# SCH_CarAccessoryKitV1_0.net
KiCad netlist of a schematic drawn in EasyEDA
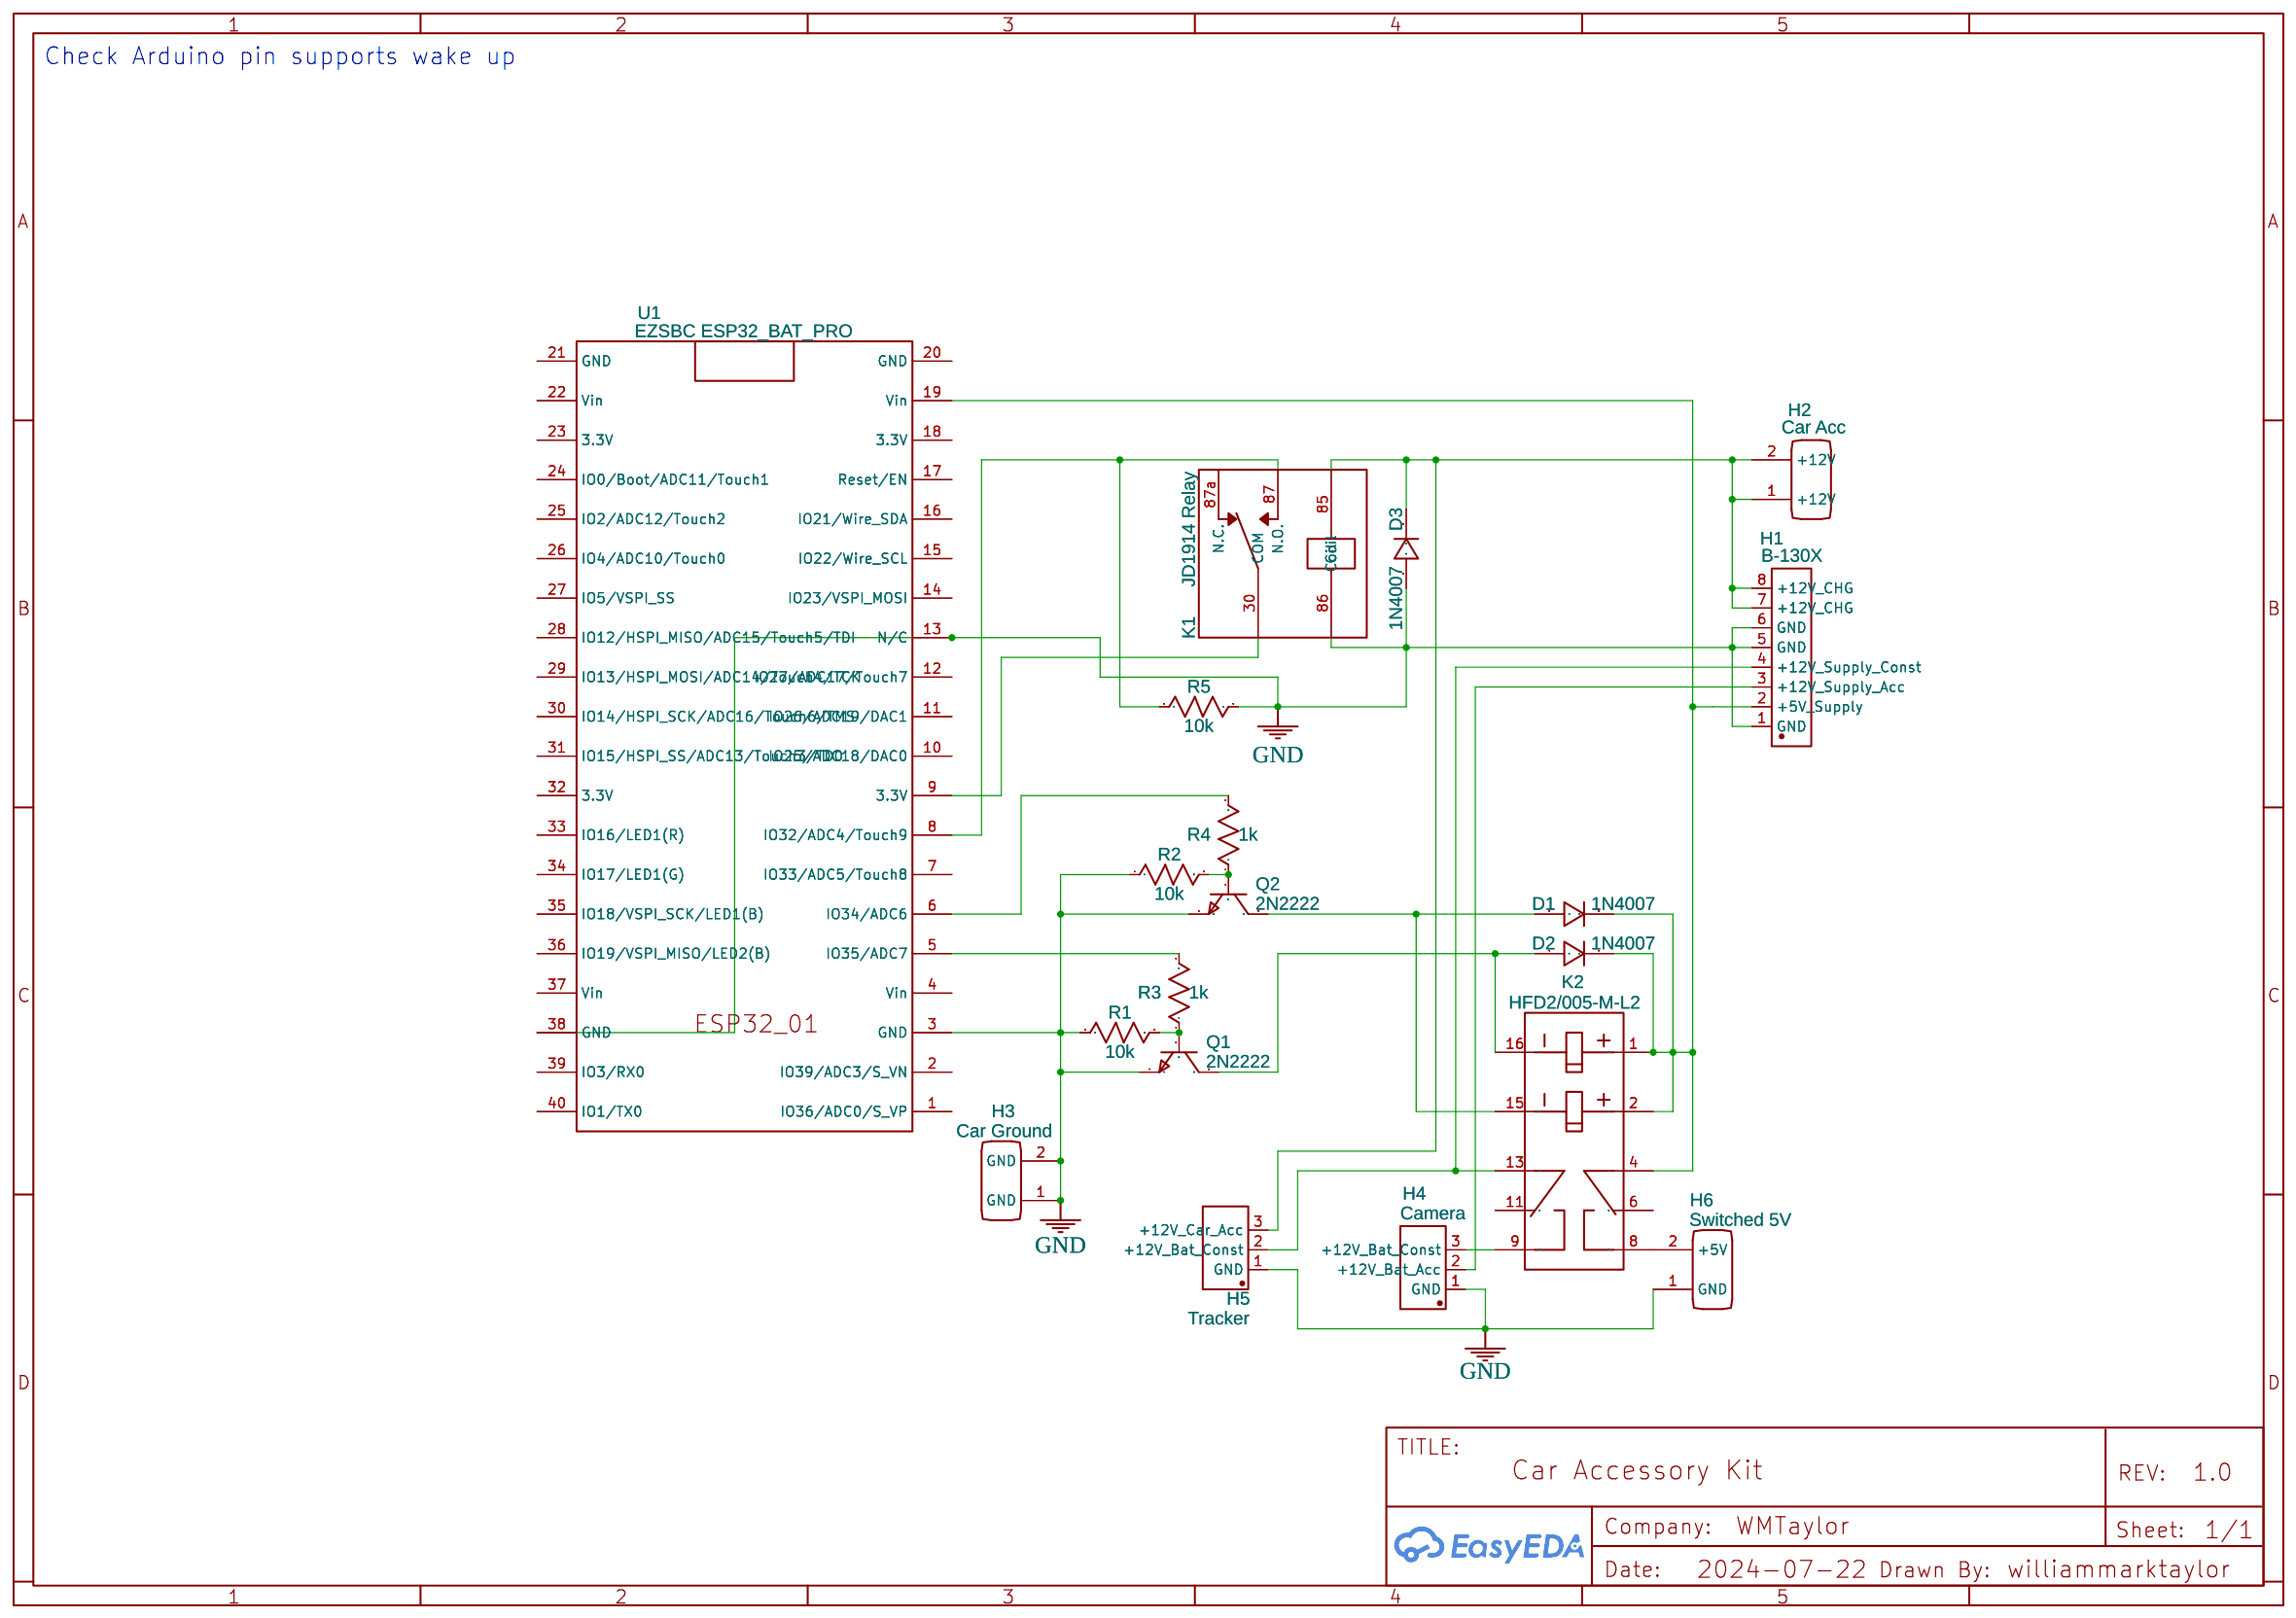
[diagram p0: schematic sheet]

(export (version "E")
  (design (tool "Eeschema 10.0.6"))
  (components
    (comp (ref "D1")
      (value "1N4007")
      (fields (field (name "Manufacturer") "SEMTECH"))
      (libsource (lib "") (part "1N4007"))
    )
    (comp (ref "D2")
      (value "1N4007")
      (fields (field (name "Manufacturer") "SEMTECH"))
      (libsource (lib "") (part "1N4007"))
    )
    (comp (ref "D3")
      (value "1N4007")
      (fields (field (name "Manufacturer") "SEMTECH"))
      (libsource (lib "") (part "1N4007_1"))
    )
    (comp (ref "H1")
      (value "B-130X")
      (fields (field (name "Manufacturer Part") "CH3.96-8A") (field (name "Manufacturer") "BOOMELE"))
      (libsource (lib "") (part "CH3.96-8A"))
    )
    (comp (ref "H2") (value "Car Acc") (libsource (lib "") (part "JST_VH-2P-3.96_1")))
    (comp (ref "H3") (value "Car Ground") (libsource (lib "") (part "JST_VH-2P-3.96_2")))
    (comp (ref "H4")
      (value "Camera")
      (fields (field (name "Manufacturer Part") "VH-3A") (field (name "Manufacturer") "BOOMELE(博穆精密)"))
      (libsource (lib "") (part "VH3.96-3A"))
    )
    (comp (ref "H5")
      (value "Tracker")
      (fields (field (name "Manufacturer Part") "VH-3A") (field (name "Manufacturer") "BOOMELE(博穆精密)"))
      (libsource (lib "") (part "VH3.96-3A_1"))
    )
    (comp (ref "H6") (value "Switched 5V") (libsource (lib "") (part "JST_VH-2P-3.96")))
    (comp (ref "K1")
      (value "JD1914 Relay")
      (fields (field (name "Manufacturer Part") "JD1914") (field (name "Manufacturer") "BenFeng"))
      (libsource (lib "") (part "RELAY JD1914 12V 80A"))
    )
    (comp (ref "K2")
      (value "HFD2/005-M-L2")
      (fields (field (name "Manufacturer") "HF(宏发)"))
      (libsource (lib "") (part "HFD2/005-M-L2"))
    )
    (comp (ref "Q1") (value "2N2222") (libsource (lib "") (part "2N2222")))
    (comp (ref "Q2") (value "2N2222") (libsource (lib "") (part "2N2222")))
    (comp (ref "R1") (value "10k") (libsource (lib "") (part "R_AXIAL-0.3_US")))
    (comp (ref "R2") (value "10k") (libsource (lib "") (part "R_AXIAL-0.3_US")))
    (comp (ref "R3") (value "1k") (libsource (lib "") (part "R_AXIAL-0.3_US_1")))
    (comp (ref "R4") (value "1k") (libsource (lib "") (part "R_AXIAL-0.3_US_1")))
    (comp (ref "R5") (value "10k") (libsource (lib "") (part "R_AXIAL-0.3_US")))
    (comp (ref "U1")
      (value "EZSBC ESP32_BAT_PRO")
      (fields (field (name "Manufacturer Part") "ESP32_01") (field (name "Manufacturer") "EZSBC"))
      (libsource (lib "") (part "EZSBC ESP32_01"))
    )
  )
  (nets
    (net (code "1") (name "GND") (class "Default")
      (node (ref "D3") (pin "2") (pinfunction "2_2") (pintype "unspecified"))
      (node (ref "H1") (pin "1") (pinfunction "GND_1") (pintype "unspecified"))
      (node (ref "H1") (pin "5") (pinfunction "GND_5") (pintype "unspecified"))
      (node (ref "H1") (pin "6") (pinfunction "GND_6") (pintype "unspecified"))
      (node (ref "H3") (pin "1") (pinfunction "GND_1") (pintype "unspecified"))
      (node (ref "H3") (pin "2") (pinfunction "GND_2") (pintype "unspecified"))
      (node (ref "H4") (pin "1") (pinfunction "GND_1") (pintype "unspecified"))
      (node (ref "H5") (pin "1") (pinfunction "GND_1") (pintype "unspecified"))
      (node (ref "H6") (pin "1") (pinfunction "GND_1") (pintype "unspecified"))
      (node (ref "K1") (pin "86") (pinfunction "Coil_86") (pintype "unspecified"))
      (node (ref "Q1") (pin "1") (pinfunction "E_1") (pintype "unspecified"))
      (node (ref "Q2") (pin "1") (pinfunction "E_1") (pintype "unspecified"))
      (node (ref "R1") (pin "1") (pinfunction "1_1") (pintype "unspecified"))
      (node (ref "R2") (pin "1") (pinfunction "1_1") (pintype "unspecified"))
      (node (ref "R5") (pin "2") (pinfunction "2_2") (pintype "unspecified"))
      (node (ref "U1") (pin "13") (pinfunction "N/C_13") (pintype "unspecified"))
      (node (ref "U1") (pin "3") (pinfunction "GND_3") (pintype "unspecified"))
      (node (ref "U1") (pin "38") (pinfunction "GND_38") (pintype "unspecified"))
    )
    (net (code "2") (name "Net-(H1-+5V_Supply)") (class "Default")
      (node (ref "D1") (pin "1") (pinfunction "1_1") (pintype "unspecified"))
      (node (ref "D2") (pin "1") (pinfunction "1_1") (pintype "unspecified"))
      (node (ref "H1") (pin "2") (pinfunction "+5V_Supply_2") (pintype "unspecified"))
      (node (ref "K2") (pin "1") (pinfunction "1_1") (pintype "unspecified"))
      (node (ref "K2") (pin "2") (pinfunction "2_2") (pintype "unspecified"))
      (node (ref "K2") (pin "4") (pinfunction "4_4") (pintype "unspecified"))
      (node (ref "U1") (pin "19") (pinfunction "Vin_19") (pintype "unspecified"))
    )
    (net (code "3") (name "Net-(H1-+12V_Supply_Acc)") (class "Default")
      (node (ref "H1") (pin "3") (pinfunction "+12V_Supply_Acc_3") (pintype "unspecified"))
      (node (ref "H4") (pin "2") (pinfunction "+12V_Bat_Acc_2") (pintype "unspecified"))
    )
    (net (code "4") (name "Net-(H1-+12V_Supply_Const)") (class "Default")
      (node (ref "H1") (pin "4") (pinfunction "+12V_Supply_Const_4") (pintype "unspecified"))
      (node (ref "H5") (pin "2") (pinfunction "+12V_Bat_Const_2") (pintype "unspecified"))
      (node (ref "K2") (pin "13") (pinfunction "13_13") (pintype "unspecified"))
    )
    (net (code "5") (name "Net-(H4-+12V_Bat_Const)") (class "Default")
      (node (ref "H4") (pin "3") (pinfunction "+12V_Bat_Const_3") (pintype "unspecified"))
      (node (ref "K2") (pin "9") (pinfunction "9_9") (pintype "unspecified"))
    )
    (net (code "6") (name "Net-(H5-+12V_Car_Acc)") (class "Default")
      (node (ref "D3") (pin "1") (pinfunction "1_1") (pintype "unspecified"))
      (node (ref "H1") (pin "7") (pinfunction "+12V_CHG_7") (pintype "unspecified"))
      (node (ref "H1") (pin "8") (pinfunction "+12V_CHG_8") (pintype "unspecified"))
      (node (ref "H2") (pin "1") (pinfunction "+12V_1") (pintype "unspecified"))
      (node (ref "H2") (pin "2") (pinfunction "+12V_2") (pintype "unspecified"))
      (node (ref "H5") (pin "3") (pinfunction "+12V_Car_Acc_3") (pintype "unspecified"))
      (node (ref "K1") (pin "85") (pinfunction "Coil_85") (pintype "unspecified"))
    )
    (net (code "7") (name "Net-(H6-+5V)") (class "Default")
      (node (ref "H6") (pin "2") (pinfunction "+5V_2") (pintype "unspecified"))
      (node (ref "K2") (pin "8") (pinfunction "8_8") (pintype "unspecified"))
    )
    (net (code "8") (name "Net-(K1-COM)") (class "Default")
      (node (ref "K1") (pin "30") (pinfunction "COM_30") (pintype "unspecified"))
      (node (ref "U1") (pin "9") (pinfunction "3.3V_9") (pintype "unspecified"))
    )
    (net (code "9") (name "Net-(K1-N.O.)") (class "Default")
      (node (ref "K1") (pin "87") (pinfunction "N.O._87") (pintype "unspecified"))
      (node (ref "R5") (pin "1") (pinfunction "1_1") (pintype "unspecified"))
      (node (ref "U1") (pin "8") (pinfunction "IO32/ADC4/Touch9_8") (pintype "unspecified"))
    )
    (net (code "10") (name "Net-(Q1-B)") (class "Default")
      (node (ref "Q1") (pin "2") (pinfunction "B_2") (pintype "unspecified"))
      (node (ref "R1") (pin "2") (pinfunction "2_2") (pintype "unspecified"))
      (node (ref "R3") (pin "1") (pinfunction "1_1") (pintype "unspecified"))
    )
    (net (code "11") (name "Net-(Q1-C)") (class "Default")
      (node (ref "D2") (pin "2") (pinfunction "2_2") (pintype "unspecified"))
      (node (ref "K2") (pin "16") (pinfunction "16_16") (pintype "unspecified"))
      (node (ref "Q1") (pin "3") (pinfunction "C_3") (pintype "unspecified"))
    )
    (net (code "12") (name "Net-(Q2-B)") (class "Default")
      (node (ref "Q2") (pin "2") (pinfunction "B_2") (pintype "unspecified"))
      (node (ref "R2") (pin "2") (pinfunction "2_2") (pintype "unspecified"))
      (node (ref "R4") (pin "1") (pinfunction "1_1") (pintype "unspecified"))
    )
    (net (code "13") (name "Net-(Q2-C)") (class "Default")
      (node (ref "D1") (pin "2") (pinfunction "2_2") (pintype "unspecified"))
      (node (ref "K2") (pin "15") (pinfunction "15_15") (pintype "unspecified"))
      (node (ref "Q2") (pin "3") (pinfunction "C_3") (pintype "unspecified"))
    )
    (net (code "14") (name "Net-(U1-IO34{slash}ADC6)") (class "Default")
      (node (ref "R4") (pin "2") (pinfunction "2_2") (pintype "unspecified"))
      (node (ref "U1") (pin "6") (pinfunction "IO34/ADC6_6") (pintype "unspecified"))
    )
    (net (code "15") (name "Net-(U1-IO35{slash}ADC7)") (class "Default")
      (node (ref "R3") (pin "2") (pinfunction "2_2") (pintype "unspecified"))
      (node (ref "U1") (pin "5") (pinfunction "IO35/ADC7_5") (pintype "unspecified"))
    )
    (net (code "16") (name "unconnected-(K1-N.C.-Pad87a)") (class "Default")
      (node (ref "K1") (pin "87a") (pinfunction "N.C._87a") (pintype "unspecified"))
    )
    (net (code "17") (name "unconnected-(K2-Pad6)") (class "Default")
      (node (ref "K2") (pin "6") (pinfunction "6_6") (pintype "unspecified"))
    )
    (net (code "18") (name "unconnected-(K2-Pad11)") (class "Default")
      (node (ref "K2") (pin "11") (pinfunction "11_11") (pintype "unspecified"))
    )
    (net (code "19") (name "unconnected-(U1-3.3V-Pad18)") (class "Default")
      (node (ref "U1") (pin "18") (pinfunction "3.3V_18") (pintype "unspecified"))
    )
    (net (code "20") (name "unconnected-(U1-3.3V-Pad23)") (class "Default")
      (node (ref "U1") (pin "23") (pinfunction "3.3V_23") (pintype "unspecified"))
    )
    (net (code "21") (name "unconnected-(U1-3.3V-Pad32)") (class "Default")
      (node (ref "U1") (pin "32") (pinfunction "3.3V_32") (pintype "unspecified"))
    )
    (net (code "22") (name "unconnected-(U1-GND-Pad20)") (class "Default")
      (node (ref "U1") (pin "20") (pinfunction "GND_20") (pintype "unspecified"))
    )
    (net (code "23") (name "unconnected-(U1-GND-Pad21)") (class "Default")
      (node (ref "U1") (pin "21") (pinfunction "GND_21") (pintype "unspecified"))
    )
    (net (code "24") (name "unconnected-(U1-IO0{slash}Boot{slash}ADC11{slash}Touch1-Pad24)") (class "Default")
      (node (ref "U1") (pin "24") (pinfunction "IO0/Boot/ADC11/Touch1_24") (pintype "unspecified"))
    )
    (net (code "25") (name "unconnected-(U1-IO1{slash}TX0-Pad40)") (class "Default")
      (node (ref "U1") (pin "40") (pinfunction "IO1/TX0_40") (pintype "unspecified"))
    )
    (net (code "26") (name "unconnected-(U1-IO2{slash}ADC12{slash}Touch2-Pad25)") (class "Default")
      (node (ref "U1") (pin "25") (pinfunction "IO2/ADC12/Touch2_25") (pintype "unspecified"))
    )
    (net (code "27") (name "unconnected-(U1-IO3{slash}RX0-Pad39)") (class "Default")
      (node (ref "U1") (pin "39") (pinfunction "IO3/RX0_39") (pintype "unspecified"))
    )
    (net (code "28") (name "unconnected-(U1-IO4{slash}ADC10{slash}Touch0-Pad26)") (class "Default")
      (node (ref "U1") (pin "26") (pinfunction "IO4/ADC10/Touch0_26") (pintype "unspecified"))
    )
    (net (code "29") (name "unconnected-(U1-IO5{slash}VSPI_SS-Pad27)") (class "Default")
      (node (ref "U1") (pin "27") (pinfunction "IO5/VSPI_SS_27") (pintype "unspecified"))
    )
    (net (code "30") (name "unconnected-(U1-IO12{slash}HSPI_MISO{slash}ADC15{slash}Touch5{slash}TDI-Pad28)") (class "Default")
      (node (ref "U1") (pin "28") (pinfunction "IO12/HSPI_MISO/ADC15/Touch5/TDI_28") (pintype "unspecified"))
    )
    (net (code "31") (name "unconnected-(U1-IO13{slash}HSPI_MOSI{slash}ADC14{slash}Touch4{slash}TCK-Pad29)") (class "Default")
      (node (ref "U1") (pin "29") (pinfunction "IO13/HSPI_MOSI/ADC14/Touch4/TCK_29") (pintype "unspecified"))
    )
    (net (code "32") (name "unconnected-(U1-IO14{slash}HSPI_SCK{slash}ADC16{slash}Touch6{slash}TMS-Pad30)") (class "Default")
      (node (ref "U1") (pin "30") (pinfunction "IO14/HSPI_SCK/ADC16/Touch6/TMS_30") (pintype "unspecified"))
    )
    (net (code "33") (name "unconnected-(U1-IO15{slash}HSPI_SS{slash}ADC13{slash}Touch3{slash}TD0-Pad31)") (class "Default")
      (node (ref "U1") (pin "31") (pinfunction "IO15/HSPI_SS/ADC13/Touch3/TD0_31") (pintype "unspecified"))
    )
    (net (code "34") (name "unconnected-(U1-IO16{slash}LED1(R)-Pad33)") (class "Default")
      (node (ref "U1") (pin "33") (pinfunction "IO16/LED1(R)_33") (pintype "unspecified"))
    )
    (net (code "35") (name "unconnected-(U1-IO17{slash}LED1(G)-Pad34)") (class "Default")
      (node (ref "U1") (pin "34") (pinfunction "IO17/LED1(G)_34") (pintype "unspecified"))
    )
    (net (code "36") (name "unconnected-(U1-IO18{slash}VSPI_SCK{slash}LED1(B)-Pad35)") (class "Default")
      (node (ref "U1") (pin "35") (pinfunction "IO18/VSPI_SCK/LED1(B)_35") (pintype "unspecified"))
    )
    (net (code "37") (name "unconnected-(U1-IO19{slash}VSPI_MISO{slash}LED2(B)-Pad36)") (class "Default")
      (node (ref "U1") (pin "36") (pinfunction "IO19/VSPI_MISO/LED2(B)_36") (pintype "unspecified"))
    )
    (net (code "38") (name "unconnected-(U1-IO21{slash}Wire_SDA-Pad16)") (class "Default")
      (node (ref "U1") (pin "16") (pinfunction "IO21/Wire_SDA_16") (pintype "unspecified"))
    )
    (net (code "39") (name "unconnected-(U1-IO22{slash}Wire_SCL-Pad15)") (class "Default")
      (node (ref "U1") (pin "15") (pinfunction "IO22/Wire_SCL_15") (pintype "unspecified"))
    )
    (net (code "40") (name "unconnected-(U1-IO23{slash}VSPI_MOSI-Pad14)") (class "Default")
      (node (ref "U1") (pin "14") (pinfunction "IO23/VSPI_MOSI_14") (pintype "unspecified"))
    )
    (net (code "41") (name "unconnected-(U1-IO25{slash}ADC18{slash}DAC0-Pad10)") (class "Default")
      (node (ref "U1") (pin "10") (pinfunction "IO25/ADC18/DAC0_10") (pintype "unspecified"))
    )
    (net (code "42") (name "unconnected-(U1-IO26{slash}ADC19{slash}DAC1-Pad11)") (class "Default")
      (node (ref "U1") (pin "11") (pinfunction "IO26/ADC19/DAC1_11") (pintype "unspecified"))
    )
    (net (code "43") (name "unconnected-(U1-IO27{slash}ADC17{slash}Touch7-Pad12)") (class "Default")
      (node (ref "U1") (pin "12") (pinfunction "IO27/ADC17/Touch7_12") (pintype "unspecified"))
    )
    (net (code "44") (name "unconnected-(U1-IO33{slash}ADC5{slash}Touch8-Pad7)") (class "Default")
      (node (ref "U1") (pin "7") (pinfunction "IO33/ADC5/Touch8_7") (pintype "unspecified"))
    )
    (net (code "45") (name "unconnected-(U1-IO36{slash}ADC0{slash}S_VP-Pad1)") (class "Default")
      (node (ref "U1") (pin "1") (pinfunction "IO36/ADC0/S_VP_1") (pintype "unspecified"))
    )
    (net (code "46") (name "unconnected-(U1-IO39{slash}ADC3{slash}S_VN-Pad2)") (class "Default")
      (node (ref "U1") (pin "2") (pinfunction "IO39/ADC3/S_VN_2") (pintype "unspecified"))
    )
    (net (code "47") (name "unconnected-(U1-Reset{slash}EN-Pad17)") (class "Default")
      (node (ref "U1") (pin "17") (pinfunction "Reset/EN_17") (pintype "unspecified"))
    )
    (net (code "48") (name "unconnected-(U1-Vin-Pad4)") (class "Default")
      (node (ref "U1") (pin "4") (pinfunction "Vin_4") (pintype "unspecified"))
    )
    (net (code "49") (name "unconnected-(U1-Vin-Pad22)") (class "Default")
      (node (ref "U1") (pin "22") (pinfunction "Vin_22") (pintype "unspecified"))
    )
    (net (code "50") (name "unconnected-(U1-Vin-Pad37)") (class "Default")
      (node (ref "U1") (pin "37") (pinfunction "Vin_37") (pintype "unspecified"))
    )
  )
)
